# pcb-breakout-skw71.net
KiCad netlist of a schematic drawn in EAGLE
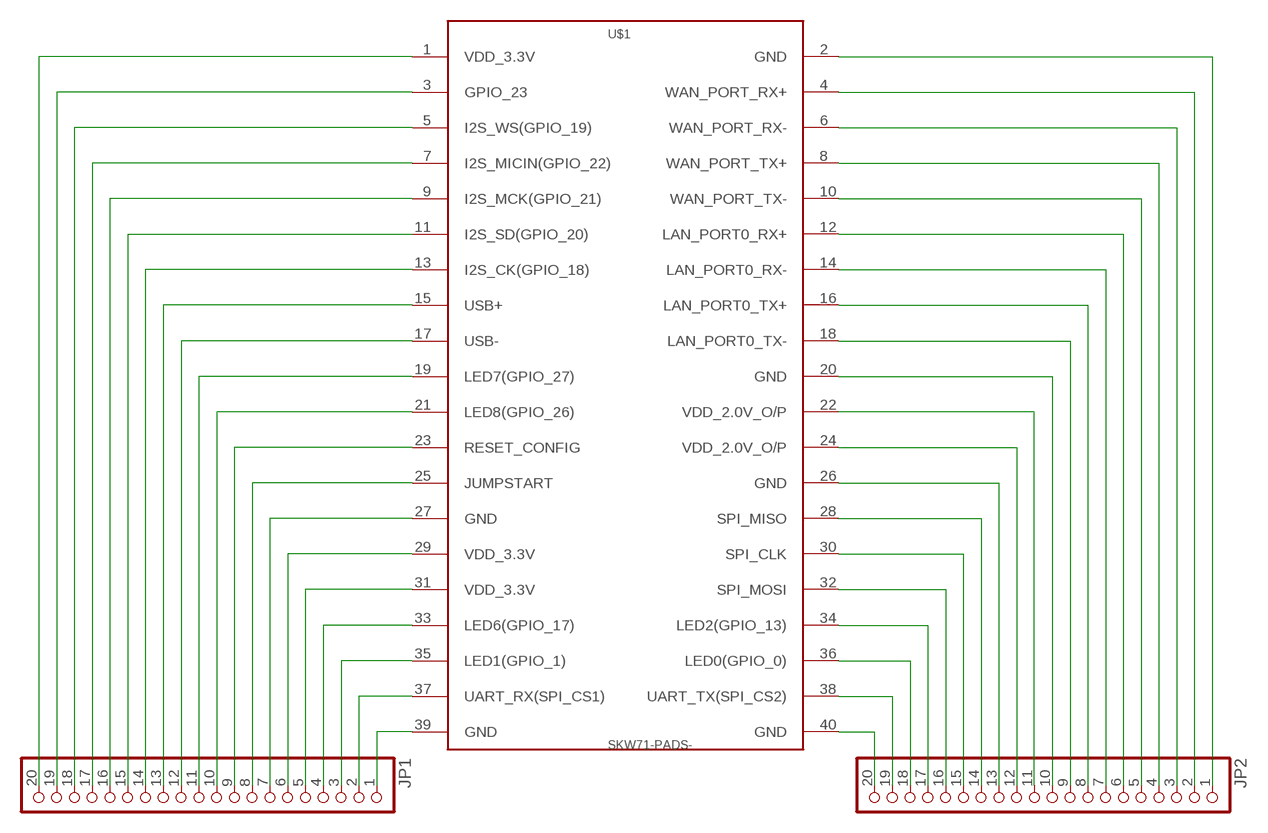
[diagram p0: schematic, sheet 1]

(export (version "E")
  (design (tool "Eeschema 10.0.6"))
  (components
    (comp (ref "JP1")
      (value "PINHD-1X20")
      (footprint "eagle-import:1X20")
      (libsource (lib "eagle-import") (part "PINHD-1X20"))
    )
    (comp (ref "JP2")
      (value "PINHD-1X20")
      (footprint "eagle-import:1X20")
      (libsource (lib "eagle-import") (part "PINHD-1X20"))
    )
    (comp (ref "U$1")
      (value "SKW71-PADS-")
      (footprint "eagle-import:SKW71-SMT")
      (libsource (lib "eagle-import") (part "SKW71-PADS-"))
    )
  )
  (nets
    (net (code "1") (name "Net-(JP1-Pad1)") (class "Default")
      (node (ref "JP1") (pin "1") (pinfunction "1_1") (pintype "passive"))
      (node (ref "U$1") (pin "39") (pinfunction "GND_39") (pintype "bidirectional"))
    )
    (net (code "2") (name "Net-(JP1-Pad5)") (class "Default")
      (node (ref "JP1") (pin "5") (pinfunction "5_5") (pintype "passive"))
      (node (ref "U$1") (pin "31") (pinfunction "VDD_3.3V_31") (pintype "bidirectional"))
    )
    (net (code "3") (name "Net-(JP1-Pad6)") (class "Default")
      (node (ref "JP1") (pin "6") (pinfunction "6_6") (pintype "passive"))
      (node (ref "U$1") (pin "29") (pinfunction "VDD_3.3V_29") (pintype "bidirectional"))
    )
    (net (code "4") (name "Net-(JP1-Pad7)") (class "Default")
      (node (ref "JP1") (pin "7") (pinfunction "7_7") (pintype "passive"))
      (node (ref "U$1") (pin "27") (pinfunction "GND_27") (pintype "bidirectional"))
    )
    (net (code "5") (name "Net-(JP1-Pad20)") (class "Default")
      (node (ref "JP1") (pin "20") (pinfunction "20_20") (pintype "passive"))
      (node (ref "U$1") (pin "1") (pinfunction "VDD_3.3V_1") (pintype "bidirectional"))
    )
    (net (code "6") (name "Net-(JP2-Pad1)") (class "Default")
      (node (ref "JP2") (pin "1") (pinfunction "1_1") (pintype "passive"))
      (node (ref "U$1") (pin "2") (pinfunction "GND_2") (pintype "bidirectional"))
    )
    (net (code "7") (name "Net-(JP2-Pad10)") (class "Default")
      (node (ref "JP2") (pin "10") (pinfunction "10_10") (pintype "passive"))
      (node (ref "U$1") (pin "20") (pinfunction "GND_20") (pintype "bidirectional"))
    )
    (net (code "8") (name "Net-(JP2-Pad11)") (class "Default")
      (node (ref "JP2") (pin "11") (pinfunction "11_11") (pintype "passive"))
      (node (ref "U$1") (pin "22") (pinfunction "VDD_2.0V_O/P_22") (pintype "bidirectional"))
    )
    (net (code "9") (name "Net-(JP2-Pad12)") (class "Default")
      (node (ref "JP2") (pin "12") (pinfunction "12_12") (pintype "passive"))
      (node (ref "U$1") (pin "24") (pinfunction "VDD_2.0V_O/P_24") (pintype "bidirectional"))
    )
    (net (code "10") (name "Net-(JP2-Pad13)") (class "Default")
      (node (ref "JP2") (pin "13") (pinfunction "13_13") (pintype "passive"))
      (node (ref "U$1") (pin "26") (pinfunction "GND_26") (pintype "bidirectional"))
    )
    (net (code "11") (name "Net-(JP2-Pad20)") (class "Default")
      (node (ref "JP2") (pin "20") (pinfunction "20_20") (pintype "passive"))
      (node (ref "U$1") (pin "40") (pinfunction "GND_40") (pintype "bidirectional"))
    )
    (net (code "12") (name "Net-(U$1-GPIO_23)") (class "Default")
      (node (ref "JP1") (pin "19") (pinfunction "19_19") (pintype "passive"))
      (node (ref "U$1") (pin "3") (pinfunction "GPIO_23_3") (pintype "bidirectional"))
    )
    (net (code "13") (name "Net-(U$1-I2S_CK(GPIO_18))") (class "Default")
      (node (ref "JP1") (pin "14") (pinfunction "14_14") (pintype "passive"))
      (node (ref "U$1") (pin "13") (pinfunction "I2S_CK(GPIO_18)_13") (pintype "bidirectional"))
    )
    (net (code "14") (name "Net-(U$1-I2S_MCK(GPIO_21))") (class "Default")
      (node (ref "JP1") (pin "16") (pinfunction "16_16") (pintype "passive"))
      (node (ref "U$1") (pin "9") (pinfunction "I2S_MCK(GPIO_21)_9") (pintype "bidirectional"))
    )
    (net (code "15") (name "Net-(U$1-I2S_MICIN(GPIO_22))") (class "Default")
      (node (ref "JP1") (pin "17") (pinfunction "17_17") (pintype "passive"))
      (node (ref "U$1") (pin "7") (pinfunction "I2S_MICIN(GPIO_22)_7") (pintype "bidirectional"))
    )
    (net (code "16") (name "Net-(U$1-I2S_SD(GPIO_20))") (class "Default")
      (node (ref "JP1") (pin "15") (pinfunction "15_15") (pintype "passive"))
      (node (ref "U$1") (pin "11") (pinfunction "I2S_SD(GPIO_20)_11") (pintype "bidirectional"))
    )
    (net (code "17") (name "Net-(U$1-I2S_WS(GPIO_19))") (class "Default")
      (node (ref "JP1") (pin "18") (pinfunction "18_18") (pintype "passive"))
      (node (ref "U$1") (pin "5") (pinfunction "I2S_WS(GPIO_19)_5") (pintype "bidirectional"))
    )
    (net (code "18") (name "Net-(U$1-JUMPSTART)") (class "Default")
      (node (ref "JP1") (pin "8") (pinfunction "8_8") (pintype "passive"))
      (node (ref "U$1") (pin "25") (pinfunction "JUMPSTART_25") (pintype "bidirectional"))
    )
    (net (code "19") (name "Net-(U$1-LAN_PORT0_RX+)") (class "Default")
      (node (ref "JP2") (pin "6") (pinfunction "6_6") (pintype "passive"))
      (node (ref "U$1") (pin "12") (pinfunction "LAN_PORT0_RX+_12") (pintype "bidirectional"))
    )
    (net (code "20") (name "Net-(U$1-LAN_PORT0_RX-)") (class "Default")
      (node (ref "JP2") (pin "7") (pinfunction "7_7") (pintype "passive"))
      (node (ref "U$1") (pin "14") (pinfunction "LAN_PORT0_RX-_14") (pintype "bidirectional"))
    )
    (net (code "21") (name "Net-(U$1-LAN_PORT0_TX+)") (class "Default")
      (node (ref "JP2") (pin "8") (pinfunction "8_8") (pintype "passive"))
      (node (ref "U$1") (pin "16") (pinfunction "LAN_PORT0_TX+_16") (pintype "bidirectional"))
    )
    (net (code "22") (name "Net-(U$1-LAN_PORT0_TX-)") (class "Default")
      (node (ref "JP2") (pin "9") (pinfunction "9_9") (pintype "passive"))
      (node (ref "U$1") (pin "18") (pinfunction "LAN_PORT0_TX-_18") (pintype "bidirectional"))
    )
    (net (code "23") (name "Net-(U$1-LED0(GPIO_0))") (class "Default")
      (node (ref "JP2") (pin "18") (pinfunction "18_18") (pintype "passive"))
      (node (ref "U$1") (pin "36") (pinfunction "LED0(GPIO_0)_36") (pintype "bidirectional"))
    )
    (net (code "24") (name "Net-(U$1-LED1(GPIO_1))") (class "Default")
      (node (ref "JP1") (pin "3") (pinfunction "3_3") (pintype "passive"))
      (node (ref "U$1") (pin "35") (pinfunction "LED1(GPIO_1)_35") (pintype "bidirectional"))
    )
    (net (code "25") (name "Net-(U$1-LED2(GPIO_13))") (class "Default")
      (node (ref "JP2") (pin "17") (pinfunction "17_17") (pintype "passive"))
      (node (ref "U$1") (pin "34") (pinfunction "LED2(GPIO_13)_34") (pintype "bidirectional"))
    )
    (net (code "26") (name "Net-(U$1-LED6(GPIO_17))") (class "Default")
      (node (ref "JP1") (pin "4") (pinfunction "4_4") (pintype "passive"))
      (node (ref "U$1") (pin "33") (pinfunction "LED6(GPIO_17)_33") (pintype "bidirectional"))
    )
    (net (code "27") (name "Net-(U$1-LED7(GPIO_27))") (class "Default")
      (node (ref "JP1") (pin "11") (pinfunction "11_11") (pintype "passive"))
      (node (ref "U$1") (pin "19") (pinfunction "LED7(GPIO_27)_19") (pintype "bidirectional"))
    )
    (net (code "28") (name "Net-(U$1-LED8(GPIO_26))") (class "Default")
      (node (ref "JP1") (pin "10") (pinfunction "10_10") (pintype "passive"))
      (node (ref "U$1") (pin "21") (pinfunction "LED8(GPIO_26)_21") (pintype "bidirectional"))
    )
    (net (code "29") (name "Net-(U$1-RESET_CONFIG)") (class "Default")
      (node (ref "JP1") (pin "9") (pinfunction "9_9") (pintype "passive"))
      (node (ref "U$1") (pin "23") (pinfunction "RESET_CONFIG_23") (pintype "bidirectional"))
    )
    (net (code "30") (name "Net-(U$1-SPI_CLK)") (class "Default")
      (node (ref "JP2") (pin "15") (pinfunction "15_15") (pintype "passive"))
      (node (ref "U$1") (pin "30") (pinfunction "SPI_CLK_30") (pintype "bidirectional"))
    )
    (net (code "31") (name "Net-(U$1-SPI_MISO)") (class "Default")
      (node (ref "JP2") (pin "14") (pinfunction "14_14") (pintype "passive"))
      (node (ref "U$1") (pin "28") (pinfunction "SPI_MISO_28") (pintype "bidirectional"))
    )
    (net (code "32") (name "Net-(U$1-SPI_MOSI)") (class "Default")
      (node (ref "JP2") (pin "16") (pinfunction "16_16") (pintype "passive"))
      (node (ref "U$1") (pin "32") (pinfunction "SPI_MOSI_32") (pintype "bidirectional"))
    )
    (net (code "33") (name "Net-(U$1-UART_RX(SPI_CS1))") (class "Default")
      (node (ref "JP1") (pin "2") (pinfunction "2_2") (pintype "passive"))
      (node (ref "U$1") (pin "37") (pinfunction "UART_RX(SPI_CS1)_37") (pintype "bidirectional"))
    )
    (net (code "34") (name "Net-(U$1-UART_TX(SPI_CS2))") (class "Default")
      (node (ref "JP2") (pin "19") (pinfunction "19_19") (pintype "passive"))
      (node (ref "U$1") (pin "38") (pinfunction "UART_TX(SPI_CS2)_38") (pintype "bidirectional"))
    )
    (net (code "35") (name "Net-(U$1-USB+)") (class "Default")
      (node (ref "JP1") (pin "13") (pinfunction "13_13") (pintype "passive"))
      (node (ref "U$1") (pin "15") (pinfunction "USB+_15") (pintype "bidirectional"))
    )
    (net (code "36") (name "Net-(U$1-USB-)") (class "Default")
      (node (ref "JP1") (pin "12") (pinfunction "12_12") (pintype "passive"))
      (node (ref "U$1") (pin "17") (pinfunction "USB-_17") (pintype "bidirectional"))
    )
    (net (code "37") (name "Net-(U$1-WAN_PORT_RX+)") (class "Default")
      (node (ref "JP2") (pin "2") (pinfunction "2_2") (pintype "passive"))
      (node (ref "U$1") (pin "4") (pinfunction "WAN_PORT_RX+_4") (pintype "bidirectional"))
    )
    (net (code "38") (name "Net-(U$1-WAN_PORT_RX-)") (class "Default")
      (node (ref "JP2") (pin "3") (pinfunction "3_3") (pintype "passive"))
      (node (ref "U$1") (pin "6") (pinfunction "WAN_PORT_RX-_6") (pintype "bidirectional"))
    )
    (net (code "39") (name "Net-(U$1-WAN_PORT_TX+)") (class "Default")
      (node (ref "JP2") (pin "4") (pinfunction "4_4") (pintype "passive"))
      (node (ref "U$1") (pin "8") (pinfunction "WAN_PORT_TX+_8") (pintype "bidirectional"))
    )
    (net (code "40") (name "Net-(U$1-WAN_PORT_TX-)") (class "Default")
      (node (ref "JP2") (pin "5") (pinfunction "5_5") (pintype "passive"))
      (node (ref "U$1") (pin "10") (pinfunction "WAN_PORT_TX-_10") (pintype "bidirectional"))
    )
  )
)
